# 03_Power_Switch.net
KiCad netlist of a schematic drawn in Altium Designer
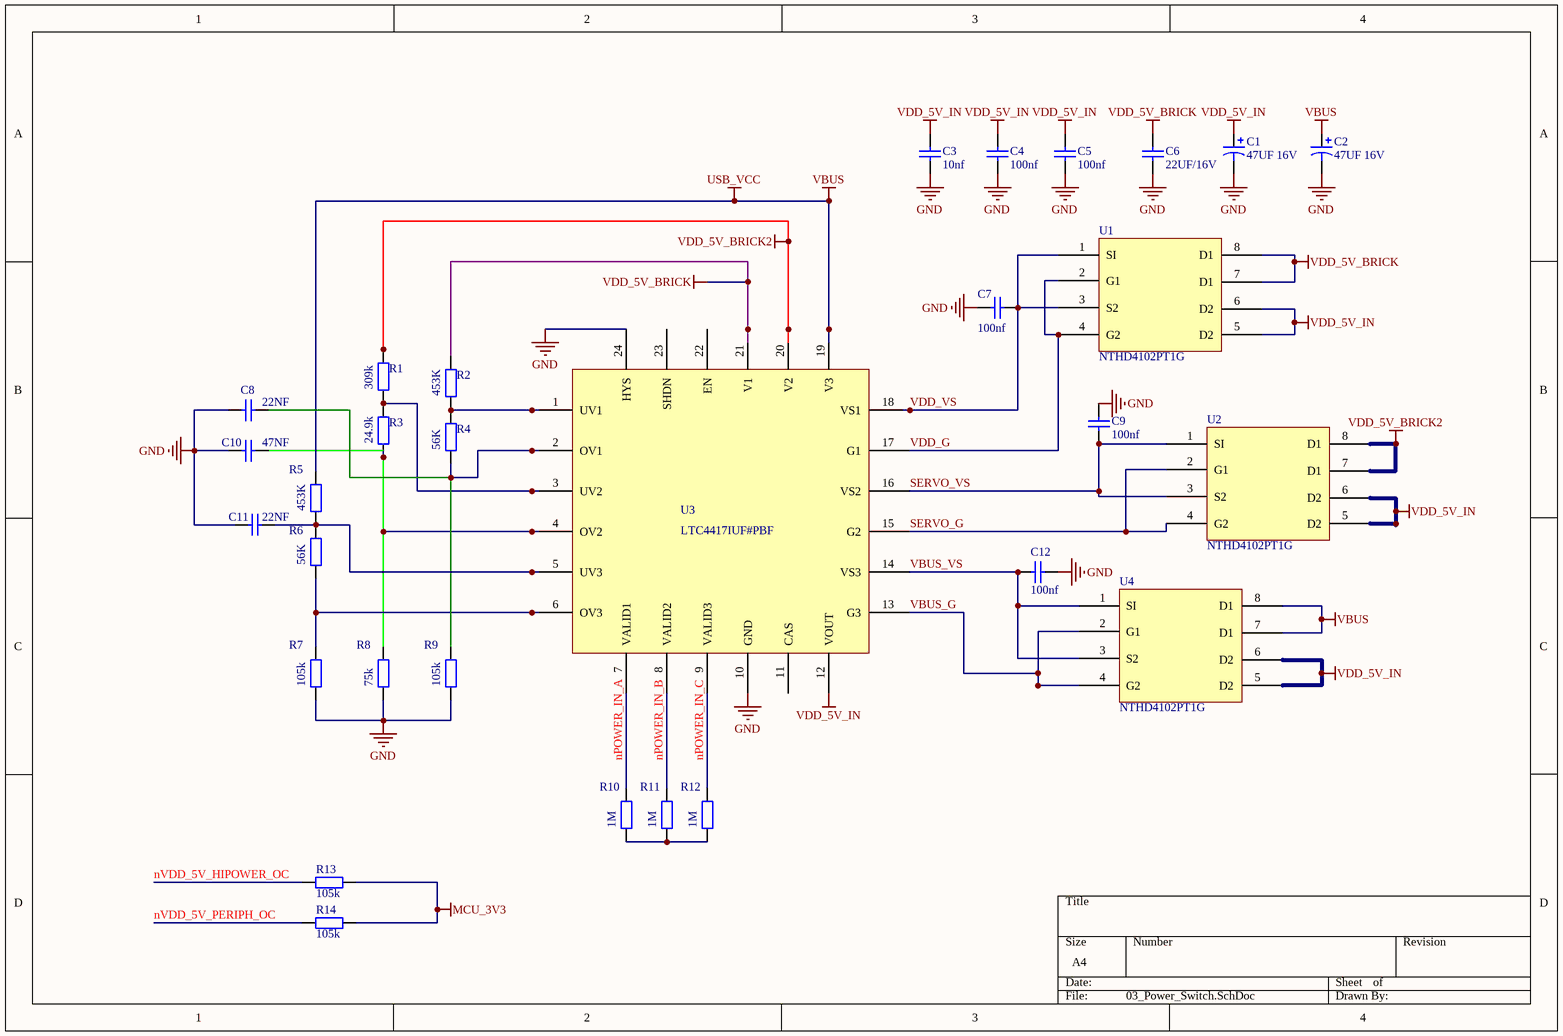
[diagram p0: 03_Power_Switch.SchDoc]

(export (version "E")
  (design (tool "Eeschema 10.0.6"))
  (components
    (comp (ref "C1")
      (value "47UF 16V")
      (footprint "7343CAP")
      (description "Polarized Capacitor (Radial)")
      (fields (field (name "PUBLISHER") "Altium Limited"))
      (libsource (lib "Miscellaneous Devices") (part "Cap Pol1"))
    )
    (comp (ref "C2")
      (value "47UF 16V")
      (footprint "7343CAP")
      (description "Polarized Capacitor (Radial)")
      (fields (field (name "PUBLISHER") "Altium Limited"))
      (libsource (lib "Miscellaneous Devices") (part "Cap Pol1"))
    )
    (comp (ref "C3")
      (value "10nf")
      (fields (field (name "PUBLISHER") "Altium Limited"))
      (libsource (lib "Miscellaneous Devices") (part "Cap"))
    )
    (comp (ref "C4")
      (value "100nf")
      (fields (field (name "PUBLISHER") "Altium Limited"))
      (libsource (lib "Miscellaneous Devices") (part "Cap"))
    )
    (comp (ref "C5")
      (value "100nf")
      (fields (field (name "PUBLISHER") "Altium Limited"))
      (libsource (lib "Miscellaneous Devices") (part "Cap"))
    )
    (comp (ref "C6")
      (value "22UF/16V")
      (fields (field (name "PUBLISHER") "Altium Limited"))
      (libsource (lib "Miscellaneous Devices") (part "Cap"))
    )
    (comp (ref "C7")
      (value "100nf")
      (fields (field (name "PUBLISHER") "Altium Limited"))
      (libsource (lib "Miscellaneous Devices") (part "Cap"))
    )
    (comp (ref "C8")
      (value "22NF")
      (fields (field (name "PUBLISHER") "Altium Limited"))
      (libsource (lib "Miscellaneous Devices") (part "Cap"))
    )
    (comp (ref "C9")
      (value "100nf")
      (fields (field (name "PUBLISHER") "Altium Limited"))
      (libsource (lib "Miscellaneous Devices") (part "Cap"))
    )
    (comp (ref "C10")
      (value "47NF")
      (fields (field (name "PUBLISHER") "Altium Limited"))
      (libsource (lib "Miscellaneous Devices") (part "Cap"))
    )
    (comp (ref "C11")
      (value "22NF")
      (fields (field (name "PUBLISHER") "Altium Limited"))
      (libsource (lib "Miscellaneous Devices") (part "Cap"))
    )
    (comp (ref "C12")
      (value "100nf")
      (fields (field (name "PUBLISHER") "Altium Limited"))
      (libsource (lib "Miscellaneous Devices") (part "Cap"))
    )
    (comp (ref "R1")
      (value "309k")
      (description "Resistor")
      (fields (field (name "PUBLISHER") "Altium Limited"))
      (libsource (lib "Miscellaneous Devices") (part "Res2"))
    )
    (comp (ref "R2")
      (value "453K")
      (description "Resistor")
      (fields (field (name "PUBLISHER") "Altium Limited"))
      (libsource (lib "Miscellaneous Devices") (part "Res2"))
    )
    (comp (ref "R3")
      (value "24.9k")
      (description "Resistor")
      (fields (field (name "PUBLISHER") "Altium Limited"))
      (libsource (lib "Miscellaneous Devices") (part "Res2"))
    )
    (comp (ref "R4")
      (value "56K")
      (description "Resistor")
      (fields (field (name "PUBLISHER") "Altium Limited"))
      (libsource (lib "Miscellaneous Devices") (part "Res2"))
    )
    (comp (ref "R5")
      (value "453K")
      (description "Resistor")
      (fields (field (name "PUBLISHER") "Altium Limited"))
      (libsource (lib "Miscellaneous Devices") (part "Res2"))
    )
    (comp (ref "R6")
      (value "56K")
      (description "Resistor")
      (fields (field (name "PUBLISHER") "Altium Limited"))
      (libsource (lib "Miscellaneous Devices") (part "Res2"))
    )
    (comp (ref "R7")
      (value "105k")
      (description "Resistor")
      (fields (field (name "PUBLISHER") "Altium Limited"))
      (libsource (lib "Miscellaneous Devices") (part "Res2"))
    )
    (comp (ref "R8")
      (value "75k")
      (description "Resistor")
      (fields (field (name "PUBLISHER") "Altium Limited"))
      (libsource (lib "Miscellaneous Devices") (part "Res2"))
    )
    (comp (ref "R9")
      (value "105k")
      (description "Resistor")
      (fields (field (name "PUBLISHER") "Altium Limited"))
      (libsource (lib "Miscellaneous Devices") (part "Res2"))
    )
    (comp (ref "R10")
      (value "1M")
      (description "Resistor")
      (fields (field (name "PUBLISHER") "Altium Limited"))
      (libsource (lib "Miscellaneous Devices") (part "Res2"))
    )
    (comp (ref "R11")
      (value "1M")
      (description "Resistor")
      (fields (field (name "PUBLISHER") "Altium Limited"))
      (libsource (lib "Miscellaneous Devices") (part "Res2"))
    )
    (comp (ref "R12")
      (value "1M")
      (description "Resistor")
      (fields (field (name "PUBLISHER") "Altium Limited"))
      (libsource (lib "Miscellaneous Devices") (part "Res2"))
    )
    (comp (ref "R13")
      (value "105k")
      (description "Resistor")
      (fields (field (name "PUBLISHER") "Altium Limited"))
      (libsource (lib "") (part "Res2_1"))
    )
    (comp (ref "R14")
      (value "105k")
      (description "Resistor")
      (fields (field (name "PUBLISHER") "Altium Limited"))
      (libsource (lib "") (part "Res2_1"))
    )
    (comp (ref "U1")
      (value "NTHD4102PT1G")
      (footprint "1206-8")
      (libsource (lib "hack") (part "NTHD4102PT1G"))
    )
    (comp (ref "U2")
      (value "NTHD4102PT1G")
      (footprint "1206-8")
      (libsource (lib "hack") (part "NTHD4102PT1G"))
    )
    (comp (ref "U3")
      (value "LTC4417IUF#PBF")
      (footprint "QFN24")
      (libsource (lib "hack") (part "LTC4417IUF#PBF"))
    )
    (comp (ref "U4")
      (value "NTHD4102PT1G")
      (footprint "1206-8")
      (libsource (lib "hack") (part "NTHD4102PT1G"))
    )
  )
  (nets
    (net (code "1") (name "/SERVO_G") (class "Default")
      (node (ref "U2") (pin "2") (pinfunction "G1_2") (pintype "passive"))
      (node (ref "U2") (pin "4") (pinfunction "G2_4") (pintype "passive"))
      (node (ref "U3") (pin "15") (pinfunction "G2_15") (pintype "passive"))
    )
    (net (code "2") (name "/SERVO_VS") (class "Default")
      (node (ref "C9") (pin "1") (pinfunction "1_1") (pintype "passive"))
      (node (ref "U2") (pin "1") (pinfunction "SI_1") (pintype "passive"))
      (node (ref "U2") (pin "3") (pinfunction "S2_3") (pintype "passive"))
      (node (ref "U3") (pin "16") (pinfunction "VS2_16") (pintype "passive"))
    )
    (net (code "3") (name "/VBUS_G") (class "Default")
      (node (ref "U3") (pin "13") (pinfunction "G3_13") (pintype "passive"))
      (node (ref "U4") (pin "2") (pinfunction "G1_2") (pintype "passive"))
      (node (ref "U4") (pin "4") (pinfunction "G2_4") (pintype "passive"))
    )
    (net (code "4") (name "/VBUS_VS") (class "Default")
      (node (ref "C12") (pin "1") (pinfunction "1_1") (pintype "passive"))
      (node (ref "U3") (pin "14") (pinfunction "VS3_14") (pintype "passive"))
      (node (ref "U4") (pin "1") (pinfunction "SI_1") (pintype "passive"))
      (node (ref "U4") (pin "3") (pinfunction "S2_3") (pintype "passive"))
    )
    (net (code "5") (name "/VDD_G") (class "Default")
      (node (ref "U1") (pin "2") (pinfunction "G1_2") (pintype "passive"))
      (node (ref "U1") (pin "4") (pinfunction "G2_4") (pintype "passive"))
      (node (ref "U3") (pin "17") (pinfunction "G1_17") (pintype "passive"))
    )
    (net (code "6") (name "/VDD_VS") (class "Default")
      (node (ref "C7") (pin "1") (pinfunction "1_1") (pintype "passive"))
      (node (ref "U1") (pin "1") (pinfunction "SI_1") (pintype "passive"))
      (node (ref "U1") (pin "3") (pinfunction "S2_3") (pintype "passive"))
      (node (ref "U3") (pin "18") (pinfunction "VS1_18") (pintype "passive"))
    )
    (net (code "7") (name "/nPOWER_IN_A") (class "Default")
      (node (ref "R10") (pin "2") (pinfunction "2_2") (pintype "passive"))
      (node (ref "U3") (pin "7") (pinfunction "VALID1_7") (pintype "passive"))
    )
    (net (code "8") (name "/nPOWER_IN_B") (class "Default")
      (node (ref "R11") (pin "2") (pinfunction "2_2") (pintype "passive"))
      (node (ref "U3") (pin "8") (pinfunction "VALID2_8") (pintype "passive"))
    )
    (net (code "9") (name "/nPOWER_IN_C") (class "Default")
      (node (ref "R12") (pin "2") (pinfunction "2_2") (pintype "passive"))
      (node (ref "U3") (pin "9") (pinfunction "VALID3_9") (pintype "passive"))
    )
    (net (code "10") (name "/nVDD_5V_HIPOWER_OC") (class "Default")
      (node (ref "R13") (pin "1") (pinfunction "1_1") (pintype "passive"))
    )
    (net (code "11") (name "/nVDD_5V_PERIPH_OC") (class "Default")
      (node (ref "R14") (pin "1") (pinfunction "1_1") (pintype "passive"))
    )
    (net (code "12") (name "GND") (class "Default")
      (node (ref "C1") (pin "C") (pinfunction "2_C") (pintype "passive"))
      (node (ref "C10") (pin "2") (pinfunction "2_2") (pintype "passive"))
      (node (ref "C11") (pin "2") (pinfunction "2_2") (pintype "passive"))
      (node (ref "C12") (pin "2") (pinfunction "2_2") (pintype "passive"))
      (node (ref "C2") (pin "C") (pinfunction "2_C") (pintype "passive"))
      (node (ref "C3") (pin "1") (pinfunction "1_1") (pintype "passive"))
      (node (ref "C4") (pin "1") (pinfunction "1_1") (pintype "passive"))
      (node (ref "C5") (pin "1") (pinfunction "1_1") (pintype "passive"))
      (node (ref "C6") (pin "1") (pinfunction "1_1") (pintype "passive"))
      (node (ref "C7") (pin "2") (pinfunction "2_2") (pintype "passive"))
      (node (ref "C8") (pin "2") (pinfunction "2_2") (pintype "passive"))
      (node (ref "C9") (pin "2") (pinfunction "2_2") (pintype "passive"))
      (node (ref "R7") (pin "1") (pinfunction "1_1") (pintype "passive"))
      (node (ref "R8") (pin "1") (pinfunction "1_1") (pintype "passive"))
      (node (ref "R9") (pin "1") (pinfunction "1_1") (pintype "passive"))
      (node (ref "U3") (pin "10") (pinfunction "GND_10") (pintype "passive"))
      (node (ref "U3") (pin "24") (pinfunction "HYS_24") (pintype "passive"))
    )
    (net (code "13") (name "MCU_3V3") (class "Default")
      (node (ref "R13") (pin "2") (pinfunction "2_2") (pintype "passive"))
      (node (ref "R14") (pin "2") (pinfunction "2_2") (pintype "passive"))
    )
    (net (code "14") (name "Net-(R10-Pad1)") (class "Default")
      (node (ref "R10") (pin "1") (pinfunction "1_1") (pintype "passive"))
      (node (ref "R11") (pin "1") (pinfunction "1_1") (pintype "passive"))
      (node (ref "R12") (pin "1") (pinfunction "1_1") (pintype "passive"))
    )
    (net (code "15") (name "Net-(U3-OV1)") (class "Default")
      (node (ref "C8") (pin "1") (pinfunction "1_1") (pintype "passive"))
      (node (ref "R4") (pin "1") (pinfunction "1_1") (pintype "passive"))
      (node (ref "R9") (pin "2") (pinfunction "2_2") (pintype "passive"))
      (node (ref "U3") (pin "2") (pinfunction "OV1_2") (pintype "passive"))
    )
    (net (code "16") (name "Net-(U3-OV2)") (class "Default")
      (node (ref "C10") (pin "1") (pinfunction "1_1") (pintype "passive"))
      (node (ref "R3") (pin "1") (pinfunction "1_1") (pintype "passive"))
      (node (ref "R8") (pin "2") (pinfunction "2_2") (pintype "passive"))
      (node (ref "U3") (pin "4") (pinfunction "OV2_4") (pintype "passive"))
    )
    (net (code "17") (name "Net-(U3-OV3)") (class "Default")
      (node (ref "R6") (pin "1") (pinfunction "1_1") (pintype "passive"))
      (node (ref "R7") (pin "2") (pinfunction "2_2") (pintype "passive"))
      (node (ref "U3") (pin "6") (pinfunction "OV3_6") (pintype "passive"))
    )
    (net (code "18") (name "Net-(U3-UV1)") (class "Default")
      (node (ref "R2") (pin "1") (pinfunction "1_1") (pintype "passive"))
      (node (ref "R4") (pin "2") (pinfunction "2_2") (pintype "passive"))
      (node (ref "U3") (pin "1") (pinfunction "UV1_1") (pintype "passive"))
    )
    (net (code "19") (name "Net-(U3-UV2)") (class "Default")
      (node (ref "R1") (pin "1") (pinfunction "1_1") (pintype "passive"))
      (node (ref "R3") (pin "2") (pinfunction "2_2") (pintype "passive"))
      (node (ref "U3") (pin "3") (pinfunction "UV2_3") (pintype "passive"))
    )
    (net (code "20") (name "Net-(U3-UV3)") (class "Default")
      (node (ref "C11") (pin "1") (pinfunction "1_1") (pintype "passive"))
      (node (ref "R5") (pin "1") (pinfunction "1_1") (pintype "passive"))
      (node (ref "R6") (pin "2") (pinfunction "2_2") (pintype "passive"))
      (node (ref "U3") (pin "5") (pinfunction "UV3_5") (pintype "passive"))
    )
    (net (code "21") (name "USB_VCC") (class "Default")
      (node (ref "C2") (pin "A") (pinfunction "1_A") (pintype "passive"))
      (node (ref "R5") (pin "2") (pinfunction "2_2") (pintype "passive"))
      (node (ref "U3") (pin "19") (pinfunction "V3_19") (pintype "passive"))
      (node (ref "U4") (pin "7") (pinfunction "D1_7") (pintype "passive"))
      (node (ref "U4") (pin "8") (pinfunction "D1_8") (pintype "passive"))
    )
    (net (code "22") (name "VDD_5V_BRICK") (class "Default")
      (node (ref "C6") (pin "2") (pinfunction "2_2") (pintype "passive"))
      (node (ref "R2") (pin "2") (pinfunction "2_2") (pintype "passive"))
      (node (ref "U1") (pin "7") (pinfunction "D1_7") (pintype "passive"))
      (node (ref "U1") (pin "8") (pinfunction "D1_8") (pintype "passive"))
      (node (ref "U3") (pin "21") (pinfunction "V1_21") (pintype "passive"))
    )
    (net (code "23") (name "VDD_5V_BRICK2") (class "Default")
      (node (ref "R1") (pin "2") (pinfunction "2_2") (pintype "passive"))
      (node (ref "U2") (pin "7") (pinfunction "D1_7") (pintype "passive"))
      (node (ref "U2") (pin "8") (pinfunction "D1_8") (pintype "passive"))
      (node (ref "U3") (pin "20") (pinfunction "V2_20") (pintype "passive"))
    )
    (net (code "24") (name "VDD_5V_IN") (class "Default")
      (node (ref "C1") (pin "A") (pinfunction "1_A") (pintype "passive"))
      (node (ref "C3") (pin "2") (pinfunction "2_2") (pintype "passive"))
      (node (ref "C4") (pin "2") (pinfunction "2_2") (pintype "passive"))
      (node (ref "C5") (pin "2") (pinfunction "2_2") (pintype "passive"))
      (node (ref "U1") (pin "5") (pinfunction "D2_5") (pintype "passive"))
      (node (ref "U1") (pin "6") (pinfunction "D2_6") (pintype "passive"))
      (node (ref "U2") (pin "5") (pinfunction "D2_5") (pintype "passive"))
      (node (ref "U2") (pin "6") (pinfunction "D2_6") (pintype "passive"))
      (node (ref "U3") (pin "12") (pinfunction "VOUT_12") (pintype "passive"))
      (node (ref "U4") (pin "5") (pinfunction "D2_5") (pintype "passive"))
      (node (ref "U4") (pin "6") (pinfunction "D2_6") (pintype "passive"))
    )
    (net (code "25") (name "unconnected-(U3-CAS-Pad11)") (class "Default")
      (node (ref "U3") (pin "11") (pinfunction "CAS_11") (pintype "passive"))
    )
    (net (code "26") (name "unconnected-(U3-EN-Pad22)") (class "Default")
      (node (ref "U3") (pin "22") (pinfunction "EN_22") (pintype "passive"))
    )
    (net (code "27") (name "unconnected-(U3-SHDN-Pad23)") (class "Default")
      (node (ref "U3") (pin "23") (pinfunction "SHDN_23") (pintype "passive"))
    )
  )
)
